# main-board_nrf.net
KiCad netlist of a schematic drawn in EAGLE
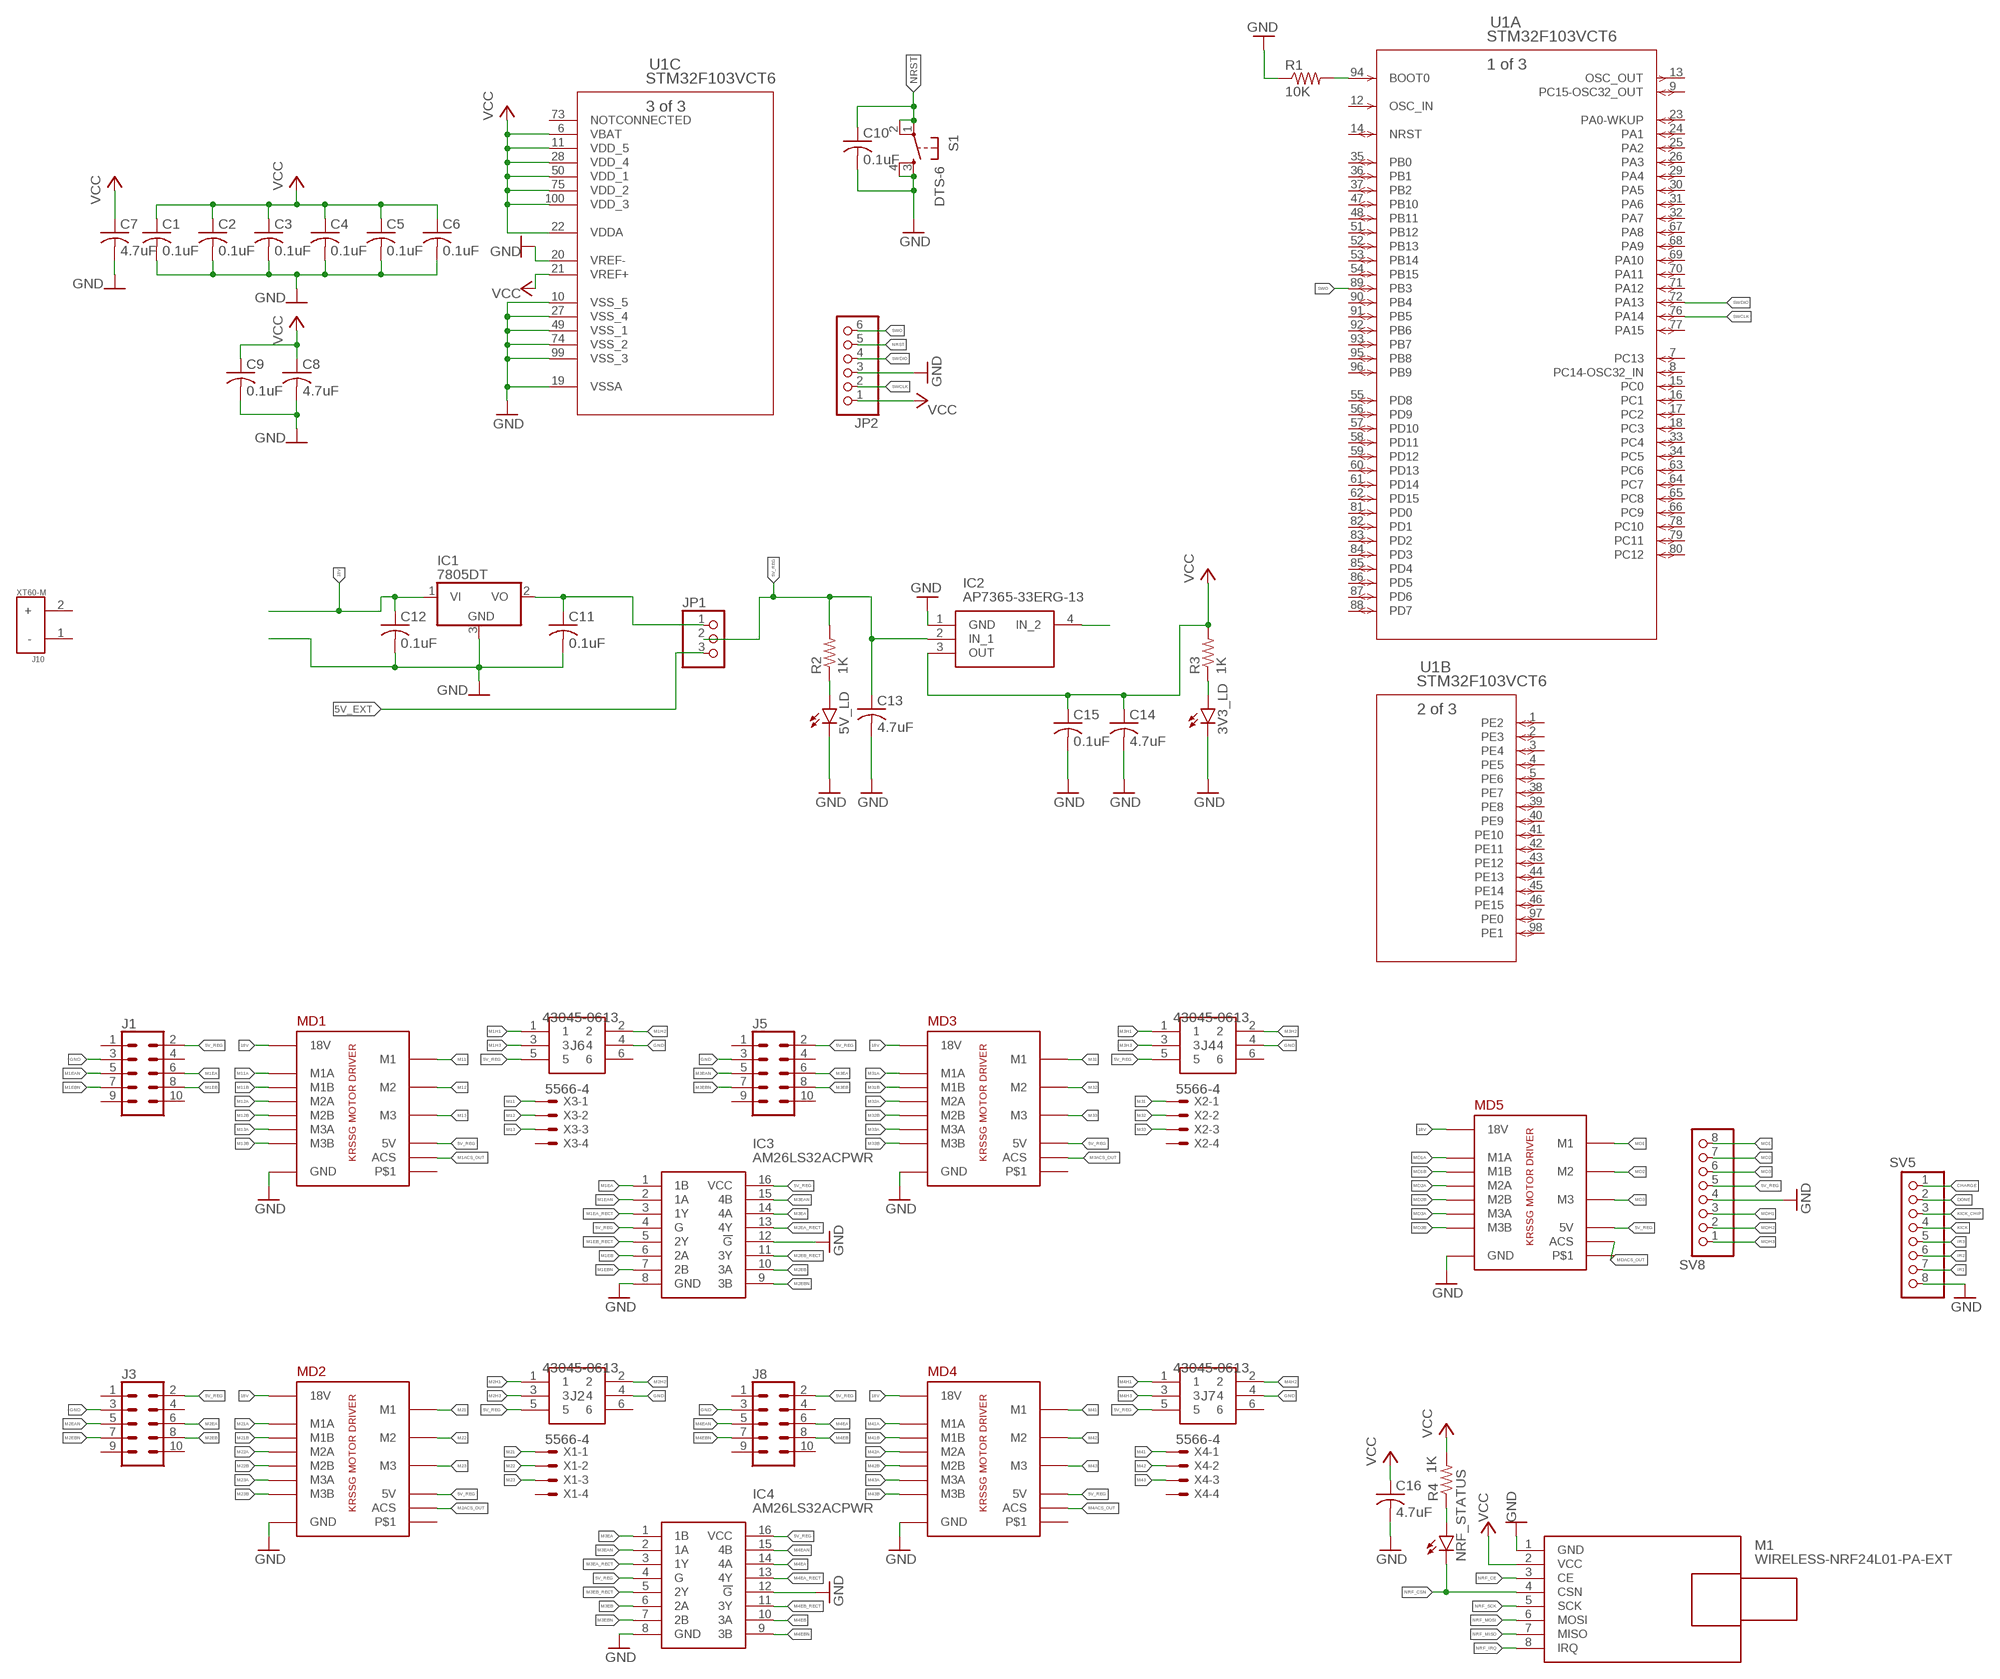
[diagram p0: schematic, sheet 1]

(export (version "E")
  (design (tool "Eeschema 10.0.6"))
  (components
    (comp (ref "3V3_LD")
      (value "LEDCHIPLED_1206")
      (footprint "eagle-import:CHIPLED_1206")
      (libsource (lib "eagle-import") (part "LEDCHIPLED_1206"))
    )
    (comp (ref "5V_LD")
      (value "LEDCHIPLED_1206")
      (footprint "eagle-import:CHIPLED_1206")
      (libsource (lib "eagle-import") (part "LEDCHIPLED_1206"))
    )
    (comp (ref "C1")
      (value "0.1uF")
      (footprint "eagle-import:C1206")
      (libsource (lib "eagle-import") (part "C-USC1206"))
    )
    (comp (ref "C2")
      (value "0.1uF")
      (footprint "eagle-import:C1206")
      (libsource (lib "eagle-import") (part "C-USC1206"))
    )
    (comp (ref "C3")
      (value "0.1uF")
      (footprint "eagle-import:C1206")
      (libsource (lib "eagle-import") (part "C-USC1206"))
    )
    (comp (ref "C4")
      (value "0.1uF")
      (footprint "eagle-import:C1206")
      (libsource (lib "eagle-import") (part "C-USC1206"))
    )
    (comp (ref "C5")
      (value "0.1uF")
      (footprint "eagle-import:C1206")
      (libsource (lib "eagle-import") (part "C-USC1206"))
    )
    (comp (ref "C6")
      (value "0.1uF")
      (footprint "eagle-import:C1206")
      (libsource (lib "eagle-import") (part "C-USC1206"))
    )
    (comp (ref "C7")
      (value "4.7uF")
      (footprint "eagle-import:C1206")
      (libsource (lib "eagle-import") (part "C-USC1206"))
    )
    (comp (ref "C8")
      (value "4.7uF")
      (footprint "eagle-import:C1206")
      (libsource (lib "eagle-import") (part "C-USC1206"))
    )
    (comp (ref "C9")
      (value "0.1uF")
      (footprint "eagle-import:C1206")
      (libsource (lib "eagle-import") (part "C-USC1206"))
    )
    (comp (ref "C10")
      (value "0.1uF")
      (footprint "eagle-import:C1206")
      (libsource (lib "eagle-import") (part "C-USC1206"))
    )
    (comp (ref "C11")
      (value "0.1uF")
      (footprint "eagle-import:C1206")
      (libsource (lib "eagle-import") (part "C-USC1206"))
    )
    (comp (ref "C12")
      (value "0.1uF")
      (footprint "eagle-import:C1206")
      (libsource (lib "eagle-import") (part "C-USC1206"))
    )
    (comp (ref "C13")
      (value "4.7uF")
      (footprint "eagle-import:C1206")
      (libsource (lib "eagle-import") (part "C-USC1206"))
    )
    (comp (ref "C14")
      (value "4.7uF")
      (footprint "eagle-import:C1206")
      (libsource (lib "eagle-import") (part "C-USC1206"))
    )
    (comp (ref "C15")
      (value "0.1uF")
      (footprint "eagle-import:C1206")
      (libsource (lib "eagle-import") (part "C-USC1206"))
    )
    (comp (ref "C16")
      (value "4.7uF")
      (footprint "eagle-import:C1206")
      (libsource (lib "eagle-import") (part "C-USC1206"))
    )
    (comp (ref "IC1")
      (value "7805DT")
      (footprint "eagle-import:TO252")
      (libsource (lib "eagle-import") (part "78DT05"))
    )
    (comp (ref "IC2")
      (value "AP7365-33ERG-13")
      (footprint "eagle-import:SOT230P700X180-4N")
      (libsource (lib "eagle-import") (part "AP7365-33ERG-13"))
    )
    (comp (ref "IC3")
      (value "AM26LS32ACPWR")
      (footprint "eagle-import:SOP65P640X120-16N")
      (fields (field (name "MOUSER_PART_NUMBER") "595-AM26LS32ACPWR"))
      (libsource (lib "eagle-import") (part "AM26LS32ACPWR"))
    )
    (comp (ref "IC4")
      (value "AM26LS32ACPWR")
      (footprint "eagle-import:SOP65P640X120-16N")
      (fields (field (name "MOUSER_PART_NUMBER") "595-AM26LS32ACPWR"))
      (libsource (lib "eagle-import") (part "AM26LS32ACPWR"))
    )
    (comp (ref "J1")
      (value "CONN_05X2SHD_LOCK")
      (footprint "eagle-import:2X5-SHROUDED_LOCK")
      (libsource (lib "eagle-import") (part "CONN_05X2SHD_LOCK"))
    )
    (comp (ref "J2")
      (value "43045-0613")
      (footprint "eagle-import:43045-0613")
      (fields (field (name "MOUSER_PART_NUMBER") "538-43045-0613") (field (name "RS_PART_NUMBER") "6700377P"))
      (libsource (lib "eagle-import") (part "43045-0613"))
    )
    (comp (ref "J3")
      (value "CONN_05X2SHD_LOCK")
      (footprint "eagle-import:2X5-SHROUDED_LOCK")
      (libsource (lib "eagle-import") (part "CONN_05X2SHD_LOCK"))
    )
    (comp (ref "J4")
      (value "43045-0613")
      (footprint "eagle-import:43045-0613")
      (fields (field (name "MOUSER_PART_NUMBER") "538-43045-0613") (field (name "RS_PART_NUMBER") "6700377P"))
      (libsource (lib "eagle-import") (part "43045-0613"))
    )
    (comp (ref "J5")
      (value "CONN_05X2SHD_LOCK")
      (footprint "eagle-import:2X5-SHROUDED_LOCK")
      (libsource (lib "eagle-import") (part "CONN_05X2SHD_LOCK"))
    )
    (comp (ref "J6")
      (value "43045-0613")
      (footprint "eagle-import:43045-0613")
      (fields (field (name "MOUSER_PART_NUMBER") "538-43045-0613") (field (name "RS_PART_NUMBER") "6700377P"))
      (libsource (lib "eagle-import") (part "43045-0613"))
    )
    (comp (ref "J7")
      (value "43045-0613")
      (footprint "eagle-import:43045-0613")
      (fields (field (name "MOUSER_PART_NUMBER") "538-43045-0613") (field (name "RS_PART_NUMBER") "6700377P"))
      (libsource (lib "eagle-import") (part "43045-0613"))
    )
    (comp (ref "J8")
      (value "CONN_05X2SHD_LOCK")
      (footprint "eagle-import:2X5-SHROUDED_LOCK")
      (libsource (lib "eagle-import") (part "CONN_05X2SHD_LOCK"))
    )
    (comp (ref "J10")
      (value "XT60-M")
      (footprint "eagle-import:AMASS_XT60-M")
      (fields (field (name "MF") "AMASS"))
      (libsource (lib "eagle-import") (part "XT60-M"))
    )
    (comp (ref "JP1")
      (value "PINHD-1X3")
      (footprint "eagle-import:1X03")
      (libsource (lib "eagle-import") (part "PINHD-1X3"))
    )
    (comp (ref "JP2")
      (value "PINHD-1X6")
      (footprint "eagle-import:1X06")
      (libsource (lib "eagle-import") (part "PINHD-1X6"))
    )
    (comp (ref "M1")
      (value "WIRELESS-NRF24L01-PA-EXT")
      (footprint "eagle-import:WIRELESS-NRD24L01-PA-EXT")
      (libsource (lib "eagle-import") (part "WIRELESS-NRF24L01-PA-EXT"))
    )
    (comp (ref "MD1")
      (value "KRSSG_MOTOR_DRIVER")
      (footprint "eagle-import:KRSSG_MOTOR_DRIVER")
      (libsource (lib "eagle-import") (part "KRSSG_MOTOR_DRIVER"))
    )
    (comp (ref "MD2")
      (value "KRSSG_MOTOR_DRIVER")
      (footprint "eagle-import:KRSSG_MOTOR_DRIVER")
      (libsource (lib "eagle-import") (part "KRSSG_MOTOR_DRIVER"))
    )
    (comp (ref "MD3")
      (value "KRSSG_MOTOR_DRIVER")
      (footprint "eagle-import:KRSSG_MOTOR_DRIVER")
      (libsource (lib "eagle-import") (part "KRSSG_MOTOR_DRIVER"))
    )
    (comp (ref "MD4")
      (value "KRSSG_MOTOR_DRIVER")
      (footprint "eagle-import:KRSSG_MOTOR_DRIVER")
      (libsource (lib "eagle-import") (part "KRSSG_MOTOR_DRIVER"))
    )
    (comp (ref "MD5")
      (value "KRSSG_MOTOR_DRIVER")
      (footprint "eagle-import:KRSSG_MOTOR_DRIVER")
      (libsource (lib "eagle-import") (part "KRSSG_MOTOR_DRIVER"))
    )
    (comp (ref "NRF_STATUS")
      (value "LEDCHIPLED_1206")
      (footprint "eagle-import:CHIPLED_1206")
      (libsource (lib "eagle-import") (part "LEDCHIPLED_1206"))
    )
    (comp (ref "R1")
      (value "10K")
      (footprint "eagle-import:M1206")
      (libsource (lib "eagle-import") (part "R-US_M1206"))
    )
    (comp (ref "R2")
      (value "1K")
      (footprint "eagle-import:M1206")
      (libsource (lib "eagle-import") (part "R-US_M1206"))
    )
    (comp (ref "R3")
      (value "1K")
      (footprint "eagle-import:M1206")
      (libsource (lib "eagle-import") (part "R-US_M1206"))
    )
    (comp (ref "R4")
      (value "1K")
      (footprint "eagle-import:M1206")
      (libsource (lib "eagle-import") (part "R-US_M1206"))
    )
    (comp (ref "S1")
      (value "DTS-6")
      (footprint "eagle-import:DTS-6")
      (libsource (lib "eagle-import") (part "DTS-6"))
    )
    (comp (ref "SV5")
      (value "PINHD-1X8")
      (footprint "eagle-import:1X08")
      (libsource (lib "eagle-import") (part "PINHD-1X8"))
    )
    (comp (ref "SV8")
      (value "PINHD-1X8")
      (footprint "eagle-import:1X08")
      (libsource (lib "eagle-import") (part "PINHD-1X8"))
    )
    (comp (ref "U1")
      (value "STM32F103VCT6")
      (footprint "eagle-import:LQFP100-14X14MM")
      (fields (field (name "COPYRIGHT") "Copyright (C) 2022 Ultra Librarian. All rights reserved."))
      (libsource (lib "eagle-import") (part "STM32F103VCT6"))
    )
    (comp (ref "X1")
      (value "5566-4")
      (footprint "eagle-import:5566-4")
      (fields (field (name "MF") "MOLEX"))
      (libsource (lib "eagle-import") (part "5566-4"))
    )
    (comp (ref "X2")
      (value "5566-4")
      (footprint "eagle-import:5566-4")
      (fields (field (name "MF") "MOLEX"))
      (libsource (lib "eagle-import") (part "5566-4"))
    )
    (comp (ref "X3")
      (value "5566-4")
      (footprint "eagle-import:5566-4")
      (fields (field (name "MF") "MOLEX"))
      (libsource (lib "eagle-import") (part "5566-4"))
    )
    (comp (ref "X4")
      (value "5566-4")
      (footprint "eagle-import:5566-4")
      (fields (field (name "MF") "MOLEX"))
      (libsource (lib "eagle-import") (part "5566-4"))
    )
  )
  (nets
    (net (code "1") (name "5V_EXT") (class "Default")
      (node (ref "JP1") (pin "3") (pinfunction "3_3") (pintype "passive"))
    )
    (net (code "2") (name "5V_REG") (class "Default")
      (node (ref "C13") (pin "1") (pinfunction "1_1") (pintype "passive"))
      (node (ref "IC2") (pin "2") (pinfunction "IN_1_2") (pintype "input"))
      (node (ref "IC2") (pin "4") (pinfunction "IN_2_4") (pintype "input"))
      (node (ref "IC3") (pin "16") (pinfunction "VCC_16") (pintype "bidirectional"))
      (node (ref "IC3") (pin "4") (pinfunction "G_4") (pintype "bidirectional"))
      (node (ref "IC4") (pin "16") (pinfunction "VCC_16") (pintype "bidirectional"))
      (node (ref "IC4") (pin "4") (pinfunction "G_4") (pintype "bidirectional"))
      (node (ref "J1") (pin "2") (pinfunction "2_2") (pintype "passive"))
      (node (ref "J2") (pin "5") (pinfunction "5_5") (pintype "bidirectional"))
      (node (ref "J3") (pin "2") (pinfunction "2_2") (pintype "passive"))
      (node (ref "J4") (pin "5") (pinfunction "5_5") (pintype "bidirectional"))
      (node (ref "J5") (pin "2") (pinfunction "2_2") (pintype "passive"))
      (node (ref "J6") (pin "5") (pinfunction "5_5") (pintype "bidirectional"))
      (node (ref "J7") (pin "5") (pinfunction "5_5") (pintype "bidirectional"))
      (node (ref "J8") (pin "2") (pinfunction "2_2") (pintype "passive"))
      (node (ref "JP1") (pin "2") (pinfunction "2_2") (pintype "passive"))
      (node (ref "MD1") (pin "5V") (pinfunction "5V_5V") (pintype "bidirectional"))
      (node (ref "MD2") (pin "5V") (pinfunction "5V_5V") (pintype "bidirectional"))
      (node (ref "MD3") (pin "5V") (pinfunction "5V_5V") (pintype "bidirectional"))
      (node (ref "MD4") (pin "5V") (pinfunction "5V_5V") (pintype "bidirectional"))
      (node (ref "MD5") (pin "5V") (pinfunction "5V_5V") (pintype "bidirectional"))
      (node (ref "R2") (pin "2") (pinfunction "2_2") (pintype "passive"))
      (node (ref "SV8") (pin "5") (pinfunction "5_5") (pintype "passive"))
    )
    (net (code "3") (name "18V") (class "Default")
      (node (ref "C12") (pin "1") (pinfunction "1_1") (pintype "passive"))
      (node (ref "IC1") (pin "1") (pinfunction "VI_1") (pintype "input"))
      (node (ref "MD1") (pin "18V") (pinfunction "18V_18V") (pintype "power_in"))
      (node (ref "MD1") (pin "18V_2") (pinfunction "18V_18V_2") (pintype "power_in"))
      (node (ref "MD2") (pin "18V") (pinfunction "18V_18V") (pintype "power_in"))
      (node (ref "MD2") (pin "18V_2") (pinfunction "18V_18V_2") (pintype "power_in"))
      (node (ref "MD3") (pin "18V") (pinfunction "18V_18V") (pintype "power_in"))
      (node (ref "MD3") (pin "18V_2") (pinfunction "18V_18V_2") (pintype "power_in"))
      (node (ref "MD4") (pin "18V") (pinfunction "18V_18V") (pintype "power_in"))
      (node (ref "MD4") (pin "18V_2") (pinfunction "18V_18V_2") (pintype "power_in"))
      (node (ref "MD5") (pin "18V") (pinfunction "18V_18V") (pintype "power_in"))
      (node (ref "MD5") (pin "18V_2") (pinfunction "18V_18V_2") (pintype "power_in"))
    )
    (net (code "4") (name "CHARGE") (class "Default")
      (node (ref "SV5") (pin "1") (pinfunction "1_1") (pintype "passive"))
    )
    (net (code "5") (name "DONE") (class "Default")
      (node (ref "SV5") (pin "2") (pinfunction "2_2") (pintype "passive"))
    )
    (net (code "6") (name "GND") (class "Default")
      (node (ref "3V3_LD") (pin "C") (pinfunction "C_C") (pintype "passive"))
      (node (ref "5V_LD") (pin "C") (pinfunction "C_C") (pintype "passive"))
      (node (ref "C1") (pin "2") (pinfunction "2_2") (pintype "passive"))
      (node (ref "C10") (pin "2") (pinfunction "2_2") (pintype "passive"))
      (node (ref "C11") (pin "2") (pinfunction "2_2") (pintype "passive"))
      (node (ref "C12") (pin "2") (pinfunction "2_2") (pintype "passive"))
      (node (ref "C13") (pin "2") (pinfunction "2_2") (pintype "passive"))
      (node (ref "C14") (pin "2") (pinfunction "2_2") (pintype "passive"))
      (node (ref "C15") (pin "2") (pinfunction "2_2") (pintype "passive"))
      (node (ref "C16") (pin "2") (pinfunction "2_2") (pintype "passive"))
      (node (ref "C2") (pin "2") (pinfunction "2_2") (pintype "passive"))
      (node (ref "C3") (pin "2") (pinfunction "2_2") (pintype "passive"))
      (node (ref "C4") (pin "2") (pinfunction "2_2") (pintype "passive"))
      (node (ref "C5") (pin "2") (pinfunction "2_2") (pintype "passive"))
      (node (ref "C6") (pin "2") (pinfunction "2_2") (pintype "passive"))
      (node (ref "C7") (pin "2") (pinfunction "2_2") (pintype "passive"))
      (node (ref "C8") (pin "2") (pinfunction "2_2") (pintype "passive"))
      (node (ref "C9") (pin "2") (pinfunction "2_2") (pintype "passive"))
      (node (ref "IC1") (pin "3") (pinfunction "GND_3") (pintype "passive"))
      (node (ref "IC2") (pin "1") (pinfunction "GND_1") (pintype "power_in"))
      (node (ref "IC3") (pin "12") (pinfunction "~{G}_12") (pintype "bidirectional"))
      (node (ref "IC3") (pin "8") (pinfunction "GND_8") (pintype "bidirectional"))
      (node (ref "IC4") (pin "12") (pinfunction "~{G}_12") (pintype "bidirectional"))
      (node (ref "IC4") (pin "8") (pinfunction "GND_8") (pintype "bidirectional"))
      (node (ref "J1") (pin "3") (pinfunction "3_3") (pintype "passive"))
      (node (ref "J2") (pin "4") (pinfunction "4_4") (pintype "bidirectional"))
      (node (ref "J3") (pin "3") (pinfunction "3_3") (pintype "passive"))
      (node (ref "J4") (pin "4") (pinfunction "4_4") (pintype "bidirectional"))
      (node (ref "J5") (pin "3") (pinfunction "3_3") (pintype "passive"))
      (node (ref "J6") (pin "4") (pinfunction "4_4") (pintype "bidirectional"))
      (node (ref "J7") (pin "4") (pinfunction "4_4") (pintype "bidirectional"))
      (node (ref "J8") (pin "3") (pinfunction "3_3") (pintype "passive"))
      (node (ref "JP2") (pin "3") (pinfunction "3_3") (pintype "passive"))
      (node (ref "M1") (pin "1") (pinfunction "GND_1") (pintype "power_in"))
      (node (ref "MD1") (pin "GND") (pinfunction "GND_GND") (pintype "power_in"))
      (node (ref "MD1") (pin "GND_2") (pinfunction "GND_GND_2") (pintype "power_in"))
      (node (ref "MD2") (pin "GND") (pinfunction "GND_GND") (pintype "power_in"))
      (node (ref "MD2") (pin "GND_2") (pinfunction "GND_GND_2") (pintype "power_in"))
      (node (ref "MD3") (pin "GND") (pinfunction "GND_GND") (pintype "power_in"))
      (node (ref "MD3") (pin "GND_2") (pinfunction "GND_GND_2") (pintype "power_in"))
      (node (ref "MD4") (pin "GND") (pinfunction "GND_GND") (pintype "power_in"))
      (node (ref "MD4") (pin "GND_2") (pinfunction "GND_GND_2") (pintype "power_in"))
      (node (ref "MD5") (pin "GND") (pinfunction "GND_GND") (pintype "power_in"))
      (node (ref "MD5") (pin "GND_2") (pinfunction "GND_GND_2") (pintype "power_in"))
      (node (ref "R1") (pin "1") (pinfunction "1_1") (pintype "passive"))
      (node (ref "S1") (pin "3") (pinfunction "3_3") (pintype "passive"))
      (node (ref "S1") (pin "4") (pinfunction "4_4") (pintype "passive"))
      (node (ref "SV5") (pin "8") (pinfunction "8_8") (pintype "passive"))
      (node (ref "SV8") (pin "4") (pinfunction "4_4") (pintype "passive"))
      (node (ref "U1") (pin "10") (pinfunction "VSS_5_10") (pintype "power_in"))
      (node (ref "U1") (pin "19") (pinfunction "VSSA_19") (pintype "power_in"))
      (node (ref "U1") (pin "20") (pinfunction "VREF-_20") (pintype "power_in"))
      (node (ref "U1") (pin "27") (pinfunction "VSS_4_27") (pintype "power_in"))
      (node (ref "U1") (pin "49") (pinfunction "VSS_1_49") (pintype "power_in"))
      (node (ref "U1") (pin "74") (pinfunction "VSS_2_74") (pintype "power_in"))
      (node (ref "U1") (pin "99") (pinfunction "VSS_3_99") (pintype "power_in"))
    )
    (net (code "7") (name "IR1") (class "Default")
      (node (ref "SV5") (pin "7") (pinfunction "7_7") (pintype "passive"))
    )
    (net (code "8") (name "IR2") (class "Default")
      (node (ref "SV5") (pin "6") (pinfunction "6_6") (pintype "passive"))
    )
    (net (code "9") (name "IR3") (class "Default")
      (node (ref "SV5") (pin "5") (pinfunction "5_5") (pintype "passive"))
    )
    (net (code "10") (name "KICK") (class "Default")
      (node (ref "SV5") (pin "4") (pinfunction "4_4") (pintype "passive"))
    )
    (net (code "11") (name "KICK_CHIP") (class "Default")
      (node (ref "SV5") (pin "3") (pinfunction "3_3") (pintype "passive"))
    )
    (net (code "12") (name "M1ACS_OUT") (class "Default")
      (node (ref "MD1") (pin "MACS_OUT") (pinfunction "ACS_MACS_OUT") (pintype "bidirectional"))
    )
    (net (code "13") (name "M1EA") (class "Default")
      (node (ref "IC3") (pin "1") (pinfunction "1B_1") (pintype "bidirectional"))
      (node (ref "J1") (pin "6") (pinfunction "6_6") (pintype "passive"))
    )
    (net (code "14") (name "M1EAN") (class "Default")
      (node (ref "IC3") (pin "2") (pinfunction "1A_2") (pintype "bidirectional"))
      (node (ref "J1") (pin "5") (pinfunction "5_5") (pintype "passive"))
    )
    (net (code "15") (name "M1EA_RECT") (class "Default")
      (node (ref "IC3") (pin "3") (pinfunction "1Y_3") (pintype "bidirectional"))
    )
    (net (code "16") (name "M1EB") (class "Default")
      (node (ref "IC3") (pin "6") (pinfunction "2A_6") (pintype "bidirectional"))
      (node (ref "J1") (pin "8") (pinfunction "8_8") (pintype "passive"))
    )
    (net (code "17") (name "M1EBN") (class "Default")
      (node (ref "IC3") (pin "7") (pinfunction "2B_7") (pintype "bidirectional"))
      (node (ref "J1") (pin "7") (pinfunction "7_7") (pintype "passive"))
    )
    (net (code "18") (name "M1EB_RECT") (class "Default")
      (node (ref "IC3") (pin "5") (pinfunction "2Y_5") (pintype "bidirectional"))
    )
    (net (code "19") (name "M1H1") (class "Default")
      (node (ref "J6") (pin "1") (pinfunction "1_1") (pintype "bidirectional"))
    )
    (net (code "20") (name "M1H2") (class "Default")
      (node (ref "J6") (pin "2") (pinfunction "2_2") (pintype "bidirectional"))
    )
    (net (code "21") (name "M1H3") (class "Default")
      (node (ref "J6") (pin "3") (pinfunction "3_3") (pintype "bidirectional"))
    )
    (net (code "22") (name "M2ACS_OUT") (class "Default")
      (node (ref "MD2") (pin "MACS_OUT") (pinfunction "ACS_MACS_OUT") (pintype "bidirectional"))
    )
    (net (code "23") (name "M2EA") (class "Default")
      (node (ref "J3") (pin "6") (pinfunction "6_6") (pintype "passive"))
    )
    (net (code "24") (name "M2EAN") (class "Default")
      (node (ref "J3") (pin "5") (pinfunction "5_5") (pintype "passive"))
    )
    (net (code "25") (name "M2EA_RECT") (class "Default")
      (node (ref "IC3") (pin "13") (pinfunction "4Y_13") (pintype "bidirectional"))
    )
    (net (code "26") (name "M2EB") (class "Default")
      (node (ref "IC3") (pin "10") (pinfunction "3A_10") (pintype "bidirectional"))
      (node (ref "J3") (pin "8") (pinfunction "8_8") (pintype "passive"))
    )
    (net (code "27") (name "M2EBN") (class "Default")
      (node (ref "IC3") (pin "9") (pinfunction "3B_9") (pintype "bidirectional"))
      (node (ref "J3") (pin "7") (pinfunction "7_7") (pintype "passive"))
    )
    (net (code "28") (name "M2EB_RECT") (class "Default")
      (node (ref "IC3") (pin "11") (pinfunction "3Y_11") (pintype "bidirectional"))
    )
    (net (code "29") (name "M2H1") (class "Default")
      (node (ref "J2") (pin "1") (pinfunction "1_1") (pintype "bidirectional"))
    )
    (net (code "30") (name "M2H2") (class "Default")
      (node (ref "J2") (pin "2") (pinfunction "2_2") (pintype "bidirectional"))
    )
    (net (code "31") (name "M2H3") (class "Default")
      (node (ref "J2") (pin "3") (pinfunction "3_3") (pintype "bidirectional"))
    )
    (net (code "32") (name "M3ACS_OUT") (class "Default")
      (node (ref "MD3") (pin "MACS_OUT") (pinfunction "ACS_MACS_OUT") (pintype "bidirectional"))
    )
    (net (code "33") (name "M3EA") (class "Default")
      (node (ref "IC3") (pin "14") (pinfunction "4A_14") (pintype "bidirectional"))
      (node (ref "IC4") (pin "1") (pinfunction "1B_1") (pintype "bidirectional"))
      (node (ref "J5") (pin "6") (pinfunction "6_6") (pintype "passive"))
    )
    (net (code "34") (name "M3EAN") (class "Default")
      (node (ref "IC3") (pin "15") (pinfunction "4B_15") (pintype "bidirectional"))
      (node (ref "IC4") (pin "2") (pinfunction "1A_2") (pintype "bidirectional"))
      (node (ref "J5") (pin "5") (pinfunction "5_5") (pintype "passive"))
    )
    (net (code "35") (name "M3EA_RECT") (class "Default")
      (node (ref "IC4") (pin "3") (pinfunction "1Y_3") (pintype "bidirectional"))
    )
    (net (code "36") (name "M3EB") (class "Default")
      (node (ref "IC4") (pin "6") (pinfunction "2A_6") (pintype "bidirectional"))
      (node (ref "J5") (pin "8") (pinfunction "8_8") (pintype "passive"))
    )
    (net (code "37") (name "M3EBN") (class "Default")
      (node (ref "IC4") (pin "7") (pinfunction "2B_7") (pintype "bidirectional"))
      (node (ref "J5") (pin "7") (pinfunction "7_7") (pintype "passive"))
    )
    (net (code "38") (name "M3EB_RECT") (class "Default")
      (node (ref "IC4") (pin "5") (pinfunction "2Y_5") (pintype "bidirectional"))
    )
    (net (code "39") (name "M3H1") (class "Default")
      (node (ref "J4") (pin "1") (pinfunction "1_1") (pintype "bidirectional"))
    )
    (net (code "40") (name "M3H2") (class "Default")
      (node (ref "J4") (pin "2") (pinfunction "2_2") (pintype "bidirectional"))
    )
    (net (code "41") (name "M3H3") (class "Default")
      (node (ref "J4") (pin "3") (pinfunction "3_3") (pintype "bidirectional"))
    )
    (net (code "42") (name "M4ACS_OUT") (class "Default")
      (node (ref "MD4") (pin "MACS_OUT") (pinfunction "ACS_MACS_OUT") (pintype "bidirectional"))
    )
    (net (code "43") (name "M4EA") (class "Default")
      (node (ref "IC4") (pin "14") (pinfunction "4A_14") (pintype "bidirectional"))
      (node (ref "J8") (pin "6") (pinfunction "6_6") (pintype "passive"))
    )
    (net (code "44") (name "M4EAN") (class "Default")
      (node (ref "IC4") (pin "15") (pinfunction "4B_15") (pintype "bidirectional"))
      (node (ref "J8") (pin "5") (pinfunction "5_5") (pintype "passive"))
    )
    (net (code "45") (name "M4EA_RECT") (class "Default")
      (node (ref "IC4") (pin "13") (pinfunction "4Y_13") (pintype "bidirectional"))
    )
    (net (code "46") (name "M4EB") (class "Default")
      (node (ref "IC4") (pin "10") (pinfunction "3A_10") (pintype "bidirectional"))
      (node (ref "J8") (pin "8") (pinfunction "8_8") (pintype "passive"))
    )
    (net (code "47") (name "M4EBN") (class "Default")
      (node (ref "IC4") (pin "9") (pinfunction "3B_9") (pintype "bidirectional"))
      (node (ref "J8") (pin "7") (pinfunction "7_7") (pintype "passive"))
    )
    (net (code "48") (name "M4EB_RECT") (class "Default")
      (node (ref "IC4") (pin "11") (pinfunction "3Y_11") (pintype "bidirectional"))
    )
    (net (code "49") (name "M4H1") (class "Default")
      (node (ref "J7") (pin "1") (pinfunction "1_1") (pintype "bidirectional"))
    )
    (net (code "50") (name "M4H2") (class "Default")
      (node (ref "J7") (pin "2") (pinfunction "2_2") (pintype "bidirectional"))
    )
    (net (code "51") (name "M4H3") (class "Default")
      (node (ref "J7") (pin "3") (pinfunction "3_3") (pintype "bidirectional"))
    )
    (net (code "52") (name "M11") (class "Default")
      (node (ref "MD1") (pin "M1") (pinfunction "M1_M1") (pintype "output"))
      (node (ref "MD1") (pin "M1_2") (pinfunction "M1_M1_2") (pintype "output"))
      (node (ref "X3") (pin "1") (pinfunction "S_1") (pintype "passive"))
    )
    (net (code "53") (name "M11A") (class "Default")
      (node (ref "MD1") (pin "M1A") (pinfunction "M1A_M1A") (pintype "input"))
    )
    (net (code "54") (name "M11B") (class "Default")
      (node (ref "MD1") (pin "M1B") (pinfunction "M1B_M1B") (pintype "input"))
    )
    (net (code "55") (name "M12") (class "Default")
      (node (ref "MD1") (pin "M2") (pinfunction "M2_M2") (pintype "output"))
      (node (ref "MD1") (pin "M2_2") (pinfunction "M2_M2_2") (pintype "output"))
      (node (ref "X3") (pin "2") (pinfunction "S_2") (pintype "passive"))
    )
    (net (code "56") (name "M12A") (class "Default")
      (node (ref "MD1") (pin "M2A") (pinfunction "M2A_M2A") (pintype "input"))
    )
    (net (code "57") (name "M12B") (class "Default")
      (node (ref "MD1") (pin "M2B") (pinfunction "M2B_M2B") (pintype "input"))
    )
    (net (code "58") (name "M13") (class "Default")
      (node (ref "MD1") (pin "M3") (pinfunction "M3_M3") (pintype "bidirectional"))
      (node (ref "MD1") (pin "M3_2") (pinfunction "M3_M3_2") (pintype "bidirectional"))
      (node (ref "X3") (pin "3") (pinfunction "S_3") (pintype "passive"))
    )
    (net (code "59") (name "M13A") (class "Default")
      (node (ref "MD1") (pin "M3A") (pinfunction "M3A_M3A") (pintype "input"))
    )
    (net (code "60") (name "M13B") (class "Default")
      (node (ref "MD1") (pin "M3B") (pinfunction "M3B_M3B") (pintype "input"))
    )
    (net (code "61") (name "M21") (class "Default")
      (node (ref "MD2") (pin "M1") (pinfunction "M1_M1") (pintype "output"))
      (node (ref "MD2") (pin "M1_2") (pinfunction "M1_M1_2") (pintype "output"))
      (node (ref "X1") (pin "1") (pinfunction "S_1") (pintype "passive"))
    )
    (net (code "62") (name "M21A") (class "Default")
      (node (ref "MD2") (pin "M1A") (pinfunction "M1A_M1A") (pintype "input"))
    )
    (net (code "63") (name "M21B") (class "Default")
      (node (ref "MD2") (pin "M1B") (pinfunction "M1B_M1B") (pintype "input"))
    )
    (net (code "64") (name "M22") (class "Default")
      (node (ref "MD2") (pin "M2") (pinfunction "M2_M2") (pintype "output"))
      (node (ref "MD2") (pin "M2_2") (pinfunction "M2_M2_2") (pintype "output"))
      (node (ref "X1") (pin "2") (pinfunction "S_2") (pintype "passive"))
    )
    (net (code "65") (name "M22A") (class "Default")
      (node (ref "MD2") (pin "M2A") (pinfunction "M2A_M2A") (pintype "input"))
    )
    (net (code "66") (name "M22B") (class "Default")
      (node (ref "MD2") (pin "M2B") (pinfunction "M2B_M2B") (pintype "input"))
    )
    (net (code "67") (name "M23") (class "Default")
      (node (ref "MD2") (pin "M3") (pinfunction "M3_M3") (pintype "bidirectional"))
      (node (ref "MD2") (pin "M3_2") (pinfunction "M3_M3_2") (pintype "bidirectional"))
      (node (ref "X1") (pin "3") (pinfunction "S_3") (pintype "passive"))
    )
    (net (code "68") (name "M23A") (class "Default")
      (node (ref "MD2") (pin "M3A") (pinfunction "M3A_M3A") (pintype "input"))
    )
    (net (code "69") (name "M23B") (class "Default")
      (node (ref "MD2") (pin "M3B") (pinfunction "M3B_M3B") (pintype "input"))
    )
    (net (code "70") (name "M31") (class "Default")
      (node (ref "MD3") (pin "M1") (pinfunction "M1_M1") (pintype "output"))
      (node (ref "MD3") (pin "M1_2") (pinfunction "M1_M1_2") (pintype "output"))
      (node (ref "X2") (pin "1") (pinfunction "S_1") (pintype "passive"))
    )
    (net (code "71") (name "M31A") (class "Default")
      (node (ref "MD3") (pin "M1A") (pinfunction "M1A_M1A") (pintype "input"))
    )
    (net (code "72") (name "M31B") (class "Default")
      (node (ref "MD3") (pin "M1B") (pinfunction "M1B_M1B") (pintype "input"))
    )
    (net (code "73") (name "M32") (class "Default")
      (node (ref "MD3") (pin "M2") (pinfunction "M2_M2") (pintype "output"))
      (node (ref "MD3") (pin "M2_2") (pinfunction "M2_M2_2") (pintype "output"))
      (node (ref "X2") (pin "2") (pinfunction "S_2") (pintype "passive"))
    )
    (net (code "74") (name "M32A") (class "Default")
      (node (ref "MD3") (pin "M2A") (pinfunction "M2A_M2A") (pintype "input"))
    )
    (net (code "75") (name "M32B") (class "Default")
      (node (ref "MD3") (pin "M2B") (pinfunction "M2B_M2B") (pintype "input"))
    )
    (net (code "76") (name "M33") (class "Default")
      (node (ref "MD3") (pin "M3") (pinfunction "M3_M3") (pintype "bidirectional"))
      (node (ref "MD3") (pin "M3_2") (pinfunction "M3_M3_2") (pintype "bidirectional"))
      (node (ref "X2") (pin "3") (pinfunction "S_3") (pintype "passive"))
    )
    (net (code "77") (name "M33A") (class "Default")
      (node (ref "MD3") (pin "M3A") (pinfunction "M3A_M3A") (pintype "input"))
    )
    (net (code "78") (name "M33B") (class "Default")
      (node (ref "MD3") (pin "M3B") (pinfunction "M3B_M3B") (pintype "input"))
    )
    (net (code "79") (name "M41") (class "Default")
      (node (ref "MD4") (pin "M1") (pinfunction "M1_M1") (pintype "output"))
      (node (ref "MD4") (pin "M1_2") (pinfunction "M1_M1_2") (pintype "output"))
      (node (ref "X4") (pin "1") (pinfunction "S_1") (pintype "passive"))
    )
    (net (code "80") (name "M41A") (class "Default")
      (node (ref "MD4") (pin "M1A") (pinfunction "M1A_M1A") (pintype "input"))
    )
    (net (code "81") (name "M41B") (class "Default")
      (node (ref "MD4") (pin "M1B") (pinfunction "M1B_M1B") (pintype "input"))
    )
    (net (code "82") (name "M42") (class "Default")
      (node (ref "MD4") (pin "M2") (pinfunction "M2_M2") (pintype "output"))
      (node (ref "MD4") (pin "M2_2") (pinfunction "M2_M2_2") (pintype "output"))
      (node (ref "X4") (pin "2") (pinfunction "S_2") (pintype "passive"))
    )
    (net (code "83") (name "M42A") (class "Default")
      (node (ref "MD4") (pin "M2A") (pinfunction "M2A_M2A") (pintype "input"))
    )
    (net (code "84") (name "M42B") (class "Default")
      (node (ref "MD4") (pin "M2B") (pinfunction "M2B_M2B") (pintype "input"))
    )
    (net (code "85") (name "M43") (class "Default")
      (node (ref "MD4") (pin "M3") (pinfunction "M3_M3") (pintype "bidirectional"))
      (node (ref "MD4") (pin "M3_2") (pinfunction "M3_M3_2") (pintype "bidirectional"))
      (node (ref "X4") (pin "3") (pinfunction "S_3") (pintype "passive"))
    )
    (net (code "86") (name "M43A") (class "Default")
      (node (ref "MD4") (pin "M3A") (pinfunction "M3A_M3A") (pintype "input"))
    )
    (net (code "87") (name "M43B") (class "Default")
      (node (ref "MD4") (pin "M3B") (pinfunction "M3B_M3B") (pintype "input"))
    )
    (net (code "88") (name "MD1") (class "Default")
      (node (ref "MD5") (pin "M1") (pinfunction "M1_M1") (pintype "output"))
      (node (ref "MD5") (pin "M1_2") (pinfunction "M1_M1_2") (pintype "output"))
      (node (ref "SV8") (pin "8") (pinfunction "8_8") (pintype "passive"))
    )
    (net (code "89") (name "MD1A") (class "Default")
      (node (ref "MD5") (pin "M1A") (pinfunction "M1A_M1A") (pintype "input"))
    )
    (net (code "90") (name "MD1B") (class "Default")
      (node (ref "MD5") (pin "M1B") (pinfunction "M1B_M1B") (pintype "input"))
    )
    (net (code "91") (name "MD2") (class "Default")
      (node (ref "MD5") (pin "M2") (pinfunction "M2_M2") (pintype "output"))
      (node (ref "MD5") (pin "M2_2") (pinfunction "M2_M2_2") (pintype "output"))
      (node (ref "SV8") (pin "7") (pinfunction "7_7") (pintype "passive"))
    )
    (net (code "92") (name "MD2A") (class "Default")
      (node (ref "MD5") (pin "M2A") (pinfunction "M2A_M2A") (pintype "input"))
    )
    (net (code "93") (name "MD2B") (class "Default")
      (node (ref "MD5") (pin "M2B") (pinfunction "M2B_M2B") (pintype "input"))
    )
    (net (code "94") (name "MD3") (class "Default")
      (node (ref "MD5") (pin "M3") (pinfunction "M3_M3") (pintype "bidirectional"))
      (node (ref "MD5") (pin "M3_2") (pinfunction "M3_M3_2") (pintype "bidirectional"))
      (node (ref "SV8") (pin "6") (pinfunction "6_6") (pintype "passive"))
    )
    (net (code "95") (name "MD3A") (class "Default")
      (node (ref "MD5") (pin "M3A") (pinfunction "M3A_M3A") (pintype "input"))
    )
    (net (code "96") (name "MD3B") (class "Default")
      (node (ref "MD5") (pin "M3B") (pinfunction "M3B_M3B") (pintype "input"))
    )
    (net (code "97") (name "MDACS_OUT") (class "Default")
      (node (ref "MD5") (pin "MACS_OUT") (pinfunction "ACS_MACS_OUT") (pintype "bidirectional"))
    )
    (net (code "98") (name "MDH1") (class "Default")
      (node (ref "SV8") (pin "3") (pinfunction "3_3") (pintype "passive"))
    )
    (net (code "99") (name "MDH2") (class "Default")
      (node (ref "SV8") (pin "2") (pinfunction "2_2") (pintype "passive"))
    )
    (net (code "100") (name "MDH3") (class "Default")
      (node (ref "SV8") (pin "1") (pinfunction "1_1") (pintype "passive"))
    )
    (net (code "101") (name "NRF_CE") (class "Default")
      (node (ref "M1") (pin "3") (pinfunction "CE_3") (pintype "bidirectional"))
    )
    (net (code "102") (name "NRF_CSN") (class "Default")
      (node (ref "M1") (pin "4") (pinfunction "CSN_4") (pintype "bidirectional"))
      (node (ref "NRF_STATUS") (pin "C") (pinfunction "C_C") (pintype "passive"))
    )
    (net (code "103") (name "NRF_IRQ") (class "Default")
      (node (ref "M1") (pin "8") (pinfunction "IRQ_8") (pintype "bidirectional"))
    )
    (net (code "104") (name "NRF_MISO") (class "Default")
      (node (ref "M1") (pin "7") (pinfunction "MISO_7") (pintype "bidirectional"))
    )
    (net (code "105") (name "NRF_MOSI") (class "Default")
      (node (ref "M1") (pin "6") (pinfunction "MOSI_6") (pintype "bidirectional"))
    )
    (net (code "106") (name "NRF_SCK") (class "Default")
      (node (ref "M1") (pin "5") (pinfunction "SCK_5") (pintype "bidirectional"))
    )
    (net (code "107") (name "NRST") (class "Default")
      (node (ref "C10") (pin "1") (pinfunction "1_1") (pintype "passive"))
      (node (ref "JP2") (pin "5") (pinfunction "5_5") (pintype "passive"))
      (node (ref "S1") (pin "1") (pinfunction "1_1") (pintype "passive"))
      (node (ref "S1") (pin "2") (pinfunction "2_2") (pintype "passive"))
    )
    (net (code "108") (name "Net-(3V3_LD-PadA)") (class "Default")
      (node (ref "3V3_LD") (pin "A") (pinfunction "A_A") (pintype "passive"))
      (node (ref "R3") (pin "1") (pinfunction "1_1") (pintype "passive"))
    )
    (net (code "109") (name "Net-(5V_LD-PadA)") (class "Default")
      (node (ref "5V_LD") (pin "A") (pinfunction "A_A") (pintype "passive"))
      (node (ref "R2") (pin "1") (pinfunction "1_1") (pintype "passive"))
    )
    (net (code "110") (name "Net-(IC1-VO)") (class "Default")
      (node (ref "C11") (pin "1") (pinfunction "1_1") (pintype "passive"))
      (node (ref "IC1") (pin "2") (pinfunction "VO_2") (pintype "passive"))
      (node (ref "JP1") (pin "1") (pinfunction "1_1") (pintype "passive"))
    )
    (net (code "111") (name "Net-(NRF_STATUS-PadA)") (class "Default")
      (node (ref "NRF_STATUS") (pin "A") (pinfunction "A_A") (pintype "passive"))
      (node (ref "R4") (pin "1") (pinfunction "1_1") (pintype "passive"))
    )
    (net (code "112") (name "Net-(U1A-BOOT0)") (class "Default")
      (node (ref "R1") (pin "2") (pinfunction "2_2") (pintype "passive"))
      (node (ref "U1") (pin "94") (pinfunction "BOOT0_94") (pintype "input"))
    )
    (net (code "113") (name "SWCLK") (class "Default")
      (node (ref "JP2") (pin "2") (pinfunction "2_2") (pintype "passive"))
      (node (ref "U1") (pin "76") (pinfunction "PA14_76") (pintype "bidirectional"))
    )
    (net (code "114") (name "SWDIO") (class "Default")
      (node (ref "JP2") (pin "4") (pinfunction "4_4") (pintype "passive"))
      (node (ref "U1") (pin "72") (pinfunction "PA13_72") (pintype "bidirectional"))
    )
    (net (code "115") (name "SWO") (class "Default")
      (node (ref "JP2") (pin "6") (pinfunction "6_6") (pintype "passive"))
      (node (ref "U1") (pin "89") (pinfunction "PB3_89") (pintype "bidirectional"))
    )
    (net (code "116") (name "VCC") (class "Default")
      (node (ref "C1") (pin "1") (pinfunction "1_1") (pintype "passive"))
      (node (ref "C14") (pin "1") (pinfunction "1_1") (pintype "passive"))
      (node (ref "C15") (pin "1") (pinfunction "1_1") (pintype "passive"))
      (node (ref "C16") (pin "1") (pinfunction "1_1") (pintype "passive"))
      (node (ref "C2") (pin "1") (pinfunction "1_1") (pintype "passive"))
      (node (ref "C3") (pin "1") (pinfunction "1_1") (pintype "passive"))
      (node (ref "C4") (pin "1") (pinfunction "1_1") (pintype "passive"))
      (node (ref "C5") (pin "1") (pinfunction "1_1") (pintype "passive"))
      (node (ref "C6") (pin "1") (pinfunction "1_1") (pintype "passive"))
      (node (ref "C7") (pin "1") (pinfunction "1_1") (pintype "passive"))
      (node (ref "C8") (pin "1") (pinfunction "1_1") (pintype "passive"))
      (node (ref "C9") (pin "1") (pinfunction "1_1") (pintype "passive"))
      (node (ref "IC2") (pin "3") (pinfunction "OUT_3") (pintype "output"))
      (node (ref "JP2") (pin "1") (pinfunction "1_1") (pintype "passive"))
      (node (ref "M1") (pin "2") (pinfunction "VCC_2") (pintype "power_in"))
      (node (ref "R3") (pin "2") (pinfunction "2_2") (pintype "passive"))
      (node (ref "R4") (pin "2") (pinfunction "2_2") (pintype "passive"))
      (node (ref "U1") (pin "100") (pinfunction "VDD_3_100") (pintype "power_in"))
      (node (ref "U1") (pin "11") (pinfunction "VDD_5_11") (pintype "power_in"))
      (node (ref "U1") (pin "21") (pinfunction "VREF+_21") (pintype "power_in"))
      (node (ref "U1") (pin "22") (pinfunction "VDDA_22") (pintype "power_in"))
      (node (ref "U1") (pin "28") (pinfunction "VDD_4_28") (pintype "power_in"))
      (node (ref "U1") (pin "50") (pinfunction "VDD_1_50") (pintype "power_in"))
      (node (ref "U1") (pin "6") (pinfunction "VBAT_6") (pintype "power_in"))
      (node (ref "U1") (pin "75") (pinfunction "VDD_2_75") (pintype "power_in"))
    )
    (net (code "117") (name "unconnected-(J1-Pad1)") (class "Default")
      (node (ref "J1") (pin "1") (pinfunction "1_1") (pintype "passive"))
    )
    (net (code "118") (name "unconnected-(J1-Pad4)") (class "Default")
      (node (ref "J1") (pin "4") (pinfunction "4_4") (pintype "passive"))
    )
    (net (code "119") (name "unconnected-(J1-Pad9)") (class "Default")
      (node (ref "J1") (pin "9") (pinfunction "9_9") (pintype "passive"))
    )
    (net (code "120") (name "unconnected-(J1-Pad10)") (class "Default")
      (node (ref "J1") (pin "10") (pinfunction "10_10") (pintype "passive"))
    )
    (net (code "121") (name "unconnected-(J2-Pad6)") (class "Default")
      (node (ref "J2") (pin "6") (pinfunction "6_6") (pintype "bidirectional"))
    )
    (net (code "122") (name "unconnected-(J3-Pad1)") (class "Default")
      (node (ref "J3") (pin "1") (pinfunction "1_1") (pintype "passive"))
    )
    (net (code "123") (name "unconnected-(J3-Pad4)") (class "Default")
      (node (ref "J3") (pin "4") (pinfunction "4_4") (pintype "passive"))
    )
    (net (code "124") (name "unconnected-(J3-Pad9)") (class "Default")
      (node (ref "J3") (pin "9") (pinfunction "9_9") (pintype "passive"))
    )
    (net (code "125") (name "unconnected-(J3-Pad10)") (class "Default")
      (node (ref "J3") (pin "10") (pinfunction "10_10") (pintype "passive"))
    )
    (net (code "126") (name "unconnected-(J4-Pad6)") (class "Default")
      (node (ref "J4") (pin "6") (pinfunction "6_6") (pintype "bidirectional"))
    )
    (net (code "127") (name "unconnected-(J5-Pad1)") (class "Default")
      (node (ref "J5") (pin "1") (pinfunction "1_1") (pintype "passive"))
    )
    (net (code "128") (name "unconnected-(J5-Pad4)") (class "Default")
      (node (ref "J5") (pin "4") (pinfunction "4_4") (pintype "passive"))
    )
    (net (code "129") (name "unconnected-(J5-Pad9)") (class "Default")
      (node (ref "J5") (pin "9") (pinfunction "9_9") (pintype "passive"))
    )
    (net (code "130") (name "unconnected-(J5-Pad10)") (class "Default")
      (node (ref "J5") (pin "10") (pinfunction "10_10") (pintype "passive"))
    )
    (net (code "131") (name "unconnected-(J6-Pad6)") (class "Default")
      (node (ref "J6") (pin "6") (pinfunction "6_6") (pintype "bidirectional"))
    )
    (net (code "132") (name "unconnected-(J7-Pad6)") (class "Default")
      (node (ref "J7") (pin "6") (pinfunction "6_6") (pintype "bidirectional"))
    )
    (net (code "133") (name "unconnected-(J8-Pad1)") (class "Default")
      (node (ref "J8") (pin "1") (pinfunction "1_1") (pintype "passive"))
    )
    (net (code "134") (name "unconnected-(J8-Pad4)") (class "Default")
      (node (ref "J8") (pin "4") (pinfunction "4_4") (pintype "passive"))
    )
    (net (code "135") (name "unconnected-(J8-Pad9)") (class "Default")
      (node (ref "J8") (pin "9") (pinfunction "9_9") (pintype "passive"))
    )
    (net (code "136") (name "unconnected-(J8-Pad10)") (class "Default")
      (node (ref "J8") (pin "10") (pinfunction "10_10") (pintype "passive"))
    )
    (net (code "137") (name "unconnected-(J10-+-Pad2)") (class "Default")
      (node (ref "J10") (pin "2") (pinfunction "+_2") (pintype "passive"))
    )
    (net (code "138") (name "unconnected-(J10---Pad1)") (class "Default")
      (node (ref "J10") (pin "1") (pinfunction "-_1") (pintype "passive"))
    )
    (net (code "139") (name "unconnected-(MD1-P$1-PadIN17)") (class "Default")
      (node (ref "MD1") (pin "IN17") (pinfunction "P$1_IN17") (pintype "no_connect"))
    )
    (net (code "140") (name "unconnected-(MD1-P$1-PadIN18)") (class "Default")
      (node (ref "MD1") (pin "IN18") (pinfunction "P$1_IN18") (pintype "no_connect"))
    )
    (net (code "141") (name "unconnected-(MD2-P$1-PadIN17)") (class "Default")
      (node (ref "MD2") (pin "IN17") (pinfunction "P$1_IN17") (pintype "no_connect"))
    )
    (net (code "142") (name "unconnected-(MD2-P$1-PadIN18)") (class "Default")
      (node (ref "MD2") (pin "IN18") (pinfunction "P$1_IN18") (pintype "no_connect"))
    )
    (net (code "143") (name "unconnected-(MD3-P$1-PadIN17)") (class "Default")
      (node (ref "MD3") (pin "IN17") (pinfunction "P$1_IN17") (pintype "no_connect"))
    )
    (net (code "144") (name "unconnected-(MD3-P$1-PadIN18)") (class "Default")
      (node (ref "MD3") (pin "IN18") (pinfunction "P$1_IN18") (pintype "no_connect"))
    )
    (net (code "145") (name "unconnected-(MD4-P$1-PadIN17)") (class "Default")
      (node (ref "MD4") (pin "IN17") (pinfunction "P$1_IN17") (pintype "no_connect"))
    )
    (net (code "146") (name "unconnected-(MD4-P$1-PadIN18)") (class "Default")
      (node (ref "MD4") (pin "IN18") (pinfunction "P$1_IN18") (pintype "no_connect"))
    )
    (net (code "147") (name "unconnected-(MD5-P$1-PadIN17)") (class "Default")
      (node (ref "MD5") (pin "IN17") (pinfunction "P$1_IN17") (pintype "no_connect"))
    )
    (net (code "148") (name "unconnected-(MD5-P$1-PadIN18)") (class "Default")
      (node (ref "MD5") (pin "IN18") (pinfunction "P$1_IN18") (pintype "no_connect"))
    )
    (net (code "149") (name "unconnected-(U1A-NRST-Pad14)") (class "Default")
      (node (ref "U1") (pin "14") (pinfunction "NRST_14") (pintype "bidirectional"))
    )
    (net (code "150") (name "unconnected-(U1A-OSC_IN-Pad12)") (class "Default")
      (node (ref "U1") (pin "12") (pinfunction "OSC_IN_12") (pintype "input"))
    )
    (net (code "151") (name "unconnected-(U1A-OSC_OUT-Pad13)") (class "Default")
      (node (ref "U1") (pin "13") (pinfunction "OSC_OUT_13") (pintype "output"))
    )
    (net (code "152") (name "unconnected-(U1A-PA0-WKUP-Pad23)") (class "Default")
      (node (ref "U1") (pin "23") (pinfunction "PA0-WKUP_23") (pintype "bidirectional"))
    )
    (net (code "153") (name "unconnected-(U1A-PA1-Pad24)") (class "Default")
      (node (ref "U1") (pin "24") (pinfunction "PA1_24") (pintype "bidirectional"))
    )
    (net (code "154") (name "unconnected-(U1A-PA2-Pad25)") (class "Default")
      (node (ref "U1") (pin "25") (pinfunction "PA2_25") (pintype "bidirectional"))
    )
    (net (code "155") (name "unconnected-(U1A-PA3-Pad26)") (class "Default")
      (node (ref "U1") (pin "26") (pinfunction "PA3_26") (pintype "bidirectional"))
    )
    (net (code "156") (name "unconnected-(U1A-PA4-Pad29)") (class "Default")
      (node (ref "U1") (pin "29") (pinfunction "PA4_29") (pintype "bidirectional"))
    )
    (net (code "157") (name "unconnected-(U1A-PA5-Pad30)") (class "Default")
      (node (ref "U1") (pin "30") (pinfunction "PA5_30") (pintype "bidirectional"))
    )
    (net (code "158") (name "unconnected-(U1A-PA6-Pad31)") (class "Default")
      (node (ref "U1") (pin "31") (pinfunction "PA6_31") (pintype "bidirectional"))
    )
    (net (code "159") (name "unconnected-(U1A-PA7-Pad32)") (class "Default")
      (node (ref "U1") (pin "32") (pinfunction "PA7_32") (pintype "bidirectional"))
    )
    (net (code "160") (name "unconnected-(U1A-PA8-Pad67)") (class "Default")
      (node (ref "U1") (pin "67") (pinfunction "PA8_67") (pintype "bidirectional"))
    )
    (net (code "161") (name "unconnected-(U1A-PA9-Pad68)") (class "Default")
      (node (ref "U1") (pin "68") (pinfunction "PA9_68") (pintype "bidirectional"))
    )
    (net (code "162") (name "unconnected-(U1A-PA10-Pad69)") (class "Default")
      (node (ref "U1") (pin "69") (pinfunction "PA10_69") (pintype "bidirectional"))
    )
    (net (code "163") (name "unconnected-(U1A-PA11-Pad70)") (class "Default")
      (node (ref "U1") (pin "70") (pinfunction "PA11_70") (pintype "bidirectional"))
    )
    (net (code "164") (name "unconnected-(U1A-PA12-Pad71)") (class "Default")
      (node (ref "U1") (pin "71") (pinfunction "PA12_71") (pintype "bidirectional"))
    )
    (net (code "165") (name "unconnected-(U1A-PA15-Pad77)") (class "Default")
      (node (ref "U1") (pin "77") (pinfunction "PA15_77") (pintype "bidirectional"))
    )
    (net (code "166") (name "unconnected-(U1A-PB0-Pad35)") (class "Default")
      (node (ref "U1") (pin "35") (pinfunction "PB0_35") (pintype "bidirectional"))
    )
    (net (code "167") (name "unconnected-(U1A-PB1-Pad36)") (class "Default")
      (node (ref "U1") (pin "36") (pinfunction "PB1_36") (pintype "bidirectional"))
    )
    (net (code "168") (name "unconnected-(U1A-PB2-Pad37)") (class "Default")
      (node (ref "U1") (pin "37") (pinfunction "PB2_37") (pintype "bidirectional"))
    )
    (net (code "169") (name "unconnected-(U1A-PB4-Pad90)") (class "Default")
      (node (ref "U1") (pin "90") (pinfunction "PB4_90") (pintype "bidirectional"))
    )
    (net (code "170") (name "unconnected-(U1A-PB5-Pad91)") (class "Default")
      (node (ref "U1") (pin "91") (pinfunction "PB5_91") (pintype "bidirectional"))
    )
    (net (code "171") (name "unconnected-(U1A-PB6-Pad92)") (class "Default")
      (node (ref "U1") (pin "92") (pinfunction "PB6_92") (pintype "bidirectional"))
    )
    (net (code "172") (name "unconnected-(U1A-PB7-Pad93)") (class "Default")
      (node (ref "U1") (pin "93") (pinfunction "PB7_93") (pintype "bidirectional"))
    )
    (net (code "173") (name "unconnected-(U1A-PB8-Pad95)") (class "Default")
      (node (ref "U1") (pin "95") (pinfunction "PB8_95") (pintype "bidirectional"))
    )
    (net (code "174") (name "unconnected-(U1A-PB9-Pad96)") (class "Default")
      (node (ref "U1") (pin "96") (pinfunction "PB9_96") (pintype "bidirectional"))
    )
    (net (code "175") (name "unconnected-(U1A-PB10-Pad47)") (class "Default")
      (node (ref "U1") (pin "47") (pinfunction "PB10_47") (pintype "bidirectional"))
    )
    (net (code "176") (name "unconnected-(U1A-PB11-Pad48)") (class "Default")
      (node (ref "U1") (pin "48") (pinfunction "PB11_48") (pintype "bidirectional"))
    )
    (net (code "177") (name "unconnected-(U1A-PB12-Pad51)") (class "Default")
      (node (ref "U1") (pin "51") (pinfunction "PB12_51") (pintype "bidirectional"))
    )
    (net (code "178") (name "unconnected-(U1A-PB13-Pad52)") (class "Default")
      (node (ref "U1") (pin "52") (pinfunction "PB13_52") (pintype "bidirectional"))
    )
    (net (code "179") (name "unconnected-(U1A-PB14-Pad53)") (class "Default")
      (node (ref "U1") (pin "53") (pinfunction "PB14_53") (pintype "bidirectional"))
    )
    (net (code "180") (name "unconnected-(U1A-PB15-Pad54)") (class "Default")
      (node (ref "U1") (pin "54") (pinfunction "PB15_54") (pintype "bidirectional"))
    )
    (net (code "181") (name "unconnected-(U1A-PC0-Pad15)") (class "Default")
      (node (ref "U1") (pin "15") (pinfunction "PC0_15") (pintype "bidirectional"))
    )
    (net (code "182") (name "unconnected-(U1A-PC1-Pad16)") (class "Default")
      (node (ref "U1") (pin "16") (pinfunction "PC1_16") (pintype "bidirectional"))
    )
    (net (code "183") (name "unconnected-(U1A-PC2-Pad17)") (class "Default")
      (node (ref "U1") (pin "17") (pinfunction "PC2_17") (pintype "bidirectional"))
    )
    (net (code "184") (name "unconnected-(U1A-PC3-Pad18)") (class "Default")
      (node (ref "U1") (pin "18") (pinfunction "PC3_18") (pintype "bidirectional"))
    )
    (net (code "185") (name "unconnected-(U1A-PC4-Pad33)") (class "Default")
      (node (ref "U1") (pin "33") (pinfunction "PC4_33") (pintype "bidirectional"))
    )
    (net (code "186") (name "unconnected-(U1A-PC5-Pad34)") (class "Default")
      (node (ref "U1") (pin "34") (pinfunction "PC5_34") (pintype "bidirectional"))
    )
    (net (code "187") (name "unconnected-(U1A-PC6-Pad63)") (class "Default")
      (node (ref "U1") (pin "63") (pinfunction "PC6_63") (pintype "bidirectional"))
    )
    (net (code "188") (name "unconnected-(U1A-PC7-Pad64)") (class "Default")
      (node (ref "U1") (pin "64") (pinfunction "PC7_64") (pintype "bidirectional"))
    )
    (net (code "189") (name "unconnected-(U1A-PC8-Pad65)") (class "Default")
      (node (ref "U1") (pin "65") (pinfunction "PC8_65") (pintype "bidirectional"))
    )
    (net (code "190") (name "unconnected-(U1A-PC9-Pad66)") (class "Default")
      (node (ref "U1") (pin "66") (pinfunction "PC9_66") (pintype "bidirectional"))
    )
    (net (code "191") (name "unconnected-(U1A-PC10-Pad78)") (class "Default")
      (node (ref "U1") (pin "78") (pinfunction "PC10_78") (pintype "bidirectional"))
    )
    (net (code "192") (name "unconnected-(U1A-PC11-Pad79)") (class "Default")
      (node (ref "U1") (pin "79") (pinfunction "PC11_79") (pintype "bidirectional"))
    )
    (net (code "193") (name "unconnected-(U1A-PC12-Pad80)") (class "Default")
      (node (ref "U1") (pin "80") (pinfunction "PC12_80") (pintype "bidirectional"))
    )
    (net (code "194") (name "unconnected-(U1A-PC13-Pad7)") (class "Default")
      (node (ref "U1") (pin "7") (pinfunction "PC13_7") (pintype "bidirectional"))
    )
    (net (code "195") (name "unconnected-(U1A-PC14-OSC32_IN-Pad8)") (class "Default")
      (node (ref "U1") (pin "8") (pinfunction "PC14-OSC32_IN_8") (pintype "bidirectional"))
    )
    (net (code "196") (name "unconnected-(U1A-PC15-OSC32_OUT-Pad9)") (class "Default")
      (node (ref "U1") (pin "9") (pinfunction "PC15-OSC32_OUT_9") (pintype "bidirectional"))
    )
    (net (code "197") (name "unconnected-(U1A-PD0-Pad81)") (class "Default")
      (node (ref "U1") (pin "81") (pinfunction "PD0_81") (pintype "bidirectional"))
    )
    (net (code "198") (name "unconnected-(U1A-PD1-Pad82)") (class "Default")
      (node (ref "U1") (pin "82") (pinfunction "PD1_82") (pintype "bidirectional"))
    )
    (net (code "199") (name "unconnected-(U1A-PD2-Pad83)") (class "Default")
      (node (ref "U1") (pin "83") (pinfunction "PD2_83") (pintype "bidirectional"))
    )
    (net (code "200") (name "unconnected-(U1A-PD3-Pad84)") (class "Default")
      (node (ref "U1") (pin "84") (pinfunction "PD3_84") (pintype "bidirectional"))
    )
    (net (code "201") (name "unconnected-(U1A-PD4-Pad85)") (class "Default")
      (node (ref "U1") (pin "85") (pinfunction "PD4_85") (pintype "bidirectional"))
    )
    (net (code "202") (name "unconnected-(U1A-PD5-Pad86)") (class "Default")
      (node (ref "U1") (pin "86") (pinfunction "PD5_86") (pintype "bidirectional"))
    )
    (net (code "203") (name "unconnected-(U1A-PD6-Pad87)") (class "Default")
      (node (ref "U1") (pin "87") (pinfunction "PD6_87") (pintype "bidirectional"))
    )
    (net (code "204") (name "unconnected-(U1A-PD7-Pad88)") (class "Default")
      (node (ref "U1") (pin "88") (pinfunction "PD7_88") (pintype "bidirectional"))
    )
    (net (code "205") (name "unconnected-(U1A-PD8-Pad55)") (class "Default")
      (node (ref "U1") (pin "55") (pinfunction "PD8_55") (pintype "bidirectional"))
    )
    (net (code "206") (name "unconnected-(U1A-PD9-Pad56)") (class "Default")
      (node (ref "U1") (pin "56") (pinfunction "PD9_56") (pintype "bidirectional"))
    )
    (net (code "207") (name "unconnected-(U1A-PD10-Pad57)") (class "Default")
      (node (ref "U1") (pin "57") (pinfunction "PD10_57") (pintype "bidirectional"))
    )
    (net (code "208") (name "unconnected-(U1A-PD11-Pad58)") (class "Default")
      (node (ref "U1") (pin "58") (pinfunction "PD11_58") (pintype "bidirectional"))
    )
    (net (code "209") (name "unconnected-(U1A-PD12-Pad59)") (class "Default")
      (node (ref "U1") (pin "59") (pinfunction "PD12_59") (pintype "bidirectional"))
    )
    (net (code "210") (name "unconnected-(U1A-PD13-Pad60)") (class "Default")
      (node (ref "U1") (pin "60") (pinfunction "PD13_60") (pintype "bidirectional"))
    )
    (net (code "211") (name "unconnected-(U1A-PD14-Pad61)") (class "Default")
      (node (ref "U1") (pin "61") (pinfunction "PD14_61") (pintype "bidirectional"))
    )
    (net (code "212") (name "unconnected-(U1A-PD15-Pad62)") (class "Default")
      (node (ref "U1") (pin "62") (pinfunction "PD15_62") (pintype "bidirectional"))
    )
    (net (code "213") (name "unconnected-(U1B-PE0-Pad97)") (class "Default")
      (node (ref "U1") (pin "97") (pinfunction "PE0_97") (pintype "bidirectional"))
    )
    (net (code "214") (name "unconnected-(U1B-PE1-Pad98)") (class "Default")
      (node (ref "U1") (pin "98") (pinfunction "PE1_98") (pintype "bidirectional"))
    )
    (net (code "215") (name "unconnected-(U1B-PE2-Pad1)") (class "Default")
      (node (ref "U1") (pin "1") (pinfunction "PE2_1") (pintype "bidirectional"))
    )
    (net (code "216") (name "unconnected-(U1B-PE3-Pad2)") (class "Default")
      (node (ref "U1") (pin "2") (pinfunction "PE3_2") (pintype "bidirectional"))
    )
    (net (code "217") (name "unconnected-(U1B-PE4-Pad3)") (class "Default")
      (node (ref "U1") (pin "3") (pinfunction "PE4_3") (pintype "bidirectional"))
    )
    (net (code "218") (name "unconnected-(U1B-PE5-Pad4)") (class "Default")
      (node (ref "U1") (pin "4") (pinfunction "PE5_4") (pintype "bidirectional"))
    )
    (net (code "219") (name "unconnected-(U1B-PE6-Pad5)") (class "Default")
      (node (ref "U1") (pin "5") (pinfunction "PE6_5") (pintype "bidirectional"))
    )
    (net (code "220") (name "unconnected-(U1B-PE7-Pad38)") (class "Default")
      (node (ref "U1") (pin "38") (pinfunction "PE7_38") (pintype "bidirectional"))
    )
    (net (code "221") (name "unconnected-(U1B-PE8-Pad39)") (class "Default")
      (node (ref "U1") (pin "39") (pinfunction "PE8_39") (pintype "bidirectional"))
    )
    (net (code "222") (name "unconnected-(U1B-PE9-Pad40)") (class "Default")
      (node (ref "U1") (pin "40") (pinfunction "PE9_40") (pintype "bidirectional"))
    )
    (net (code "223") (name "unconnected-(U1B-PE10-Pad41)") (class "Default")
      (node (ref "U1") (pin "41") (pinfunction "PE10_41") (pintype "bidirectional"))
    )
    (net (code "224") (name "unconnected-(U1B-PE11-Pad42)") (class "Default")
      (node (ref "U1") (pin "42") (pinfunction "PE11_42") (pintype "bidirectional"))
    )
    (net (code "225") (name "unconnected-(U1B-PE12-Pad43)") (class "Default")
      (node (ref "U1") (pin "43") (pinfunction "PE12_43") (pintype "bidirectional"))
    )
    (net (code "226") (name "unconnected-(U1B-PE13-Pad44)") (class "Default")
      (node (ref "U1") (pin "44") (pinfunction "PE13_44") (pintype "bidirectional"))
    )
    (net (code "227") (name "unconnected-(U1B-PE14-Pad45)") (class "Default")
      (node (ref "U1") (pin "45") (pinfunction "PE14_45") (pintype "bidirectional"))
    )
    (net (code "228") (name "unconnected-(U1B-PE15-Pad46)") (class "Default")
      (node (ref "U1") (pin "46") (pinfunction "PE15_46") (pintype "bidirectional"))
    )
    (net (code "229") (name "unconnected-(U1C-NOTCONNECTED-Pad73)") (class "Default")
      (node (ref "U1") (pin "73") (pinfunction "NOTCONNECTED_73") (pintype "no_connect"))
    )
    (net (code "230") (name "unconnected-(X1D-S-Pad4)") (class "Default")
      (node (ref "X1") (pin "4") (pinfunction "S_4") (pintype "passive"))
    )
    (net (code "231") (name "unconnected-(X2D-S-Pad4)") (class "Default")
      (node (ref "X2") (pin "4") (pinfunction "S_4") (pintype "passive"))
    )
    (net (code "232") (name "unconnected-(X3D-S-Pad4)") (class "Default")
      (node (ref "X3") (pin "4") (pinfunction "S_4") (pintype "passive"))
    )
    (net (code "233") (name "unconnected-(X4D-S-Pad4)") (class "Default")
      (node (ref "X4") (pin "4") (pinfunction "S_4") (pintype "passive"))
    )
  )
)
